# 07_-_GIGAVAC.net
KiCad netlist of a schematic drawn in Altium Designer
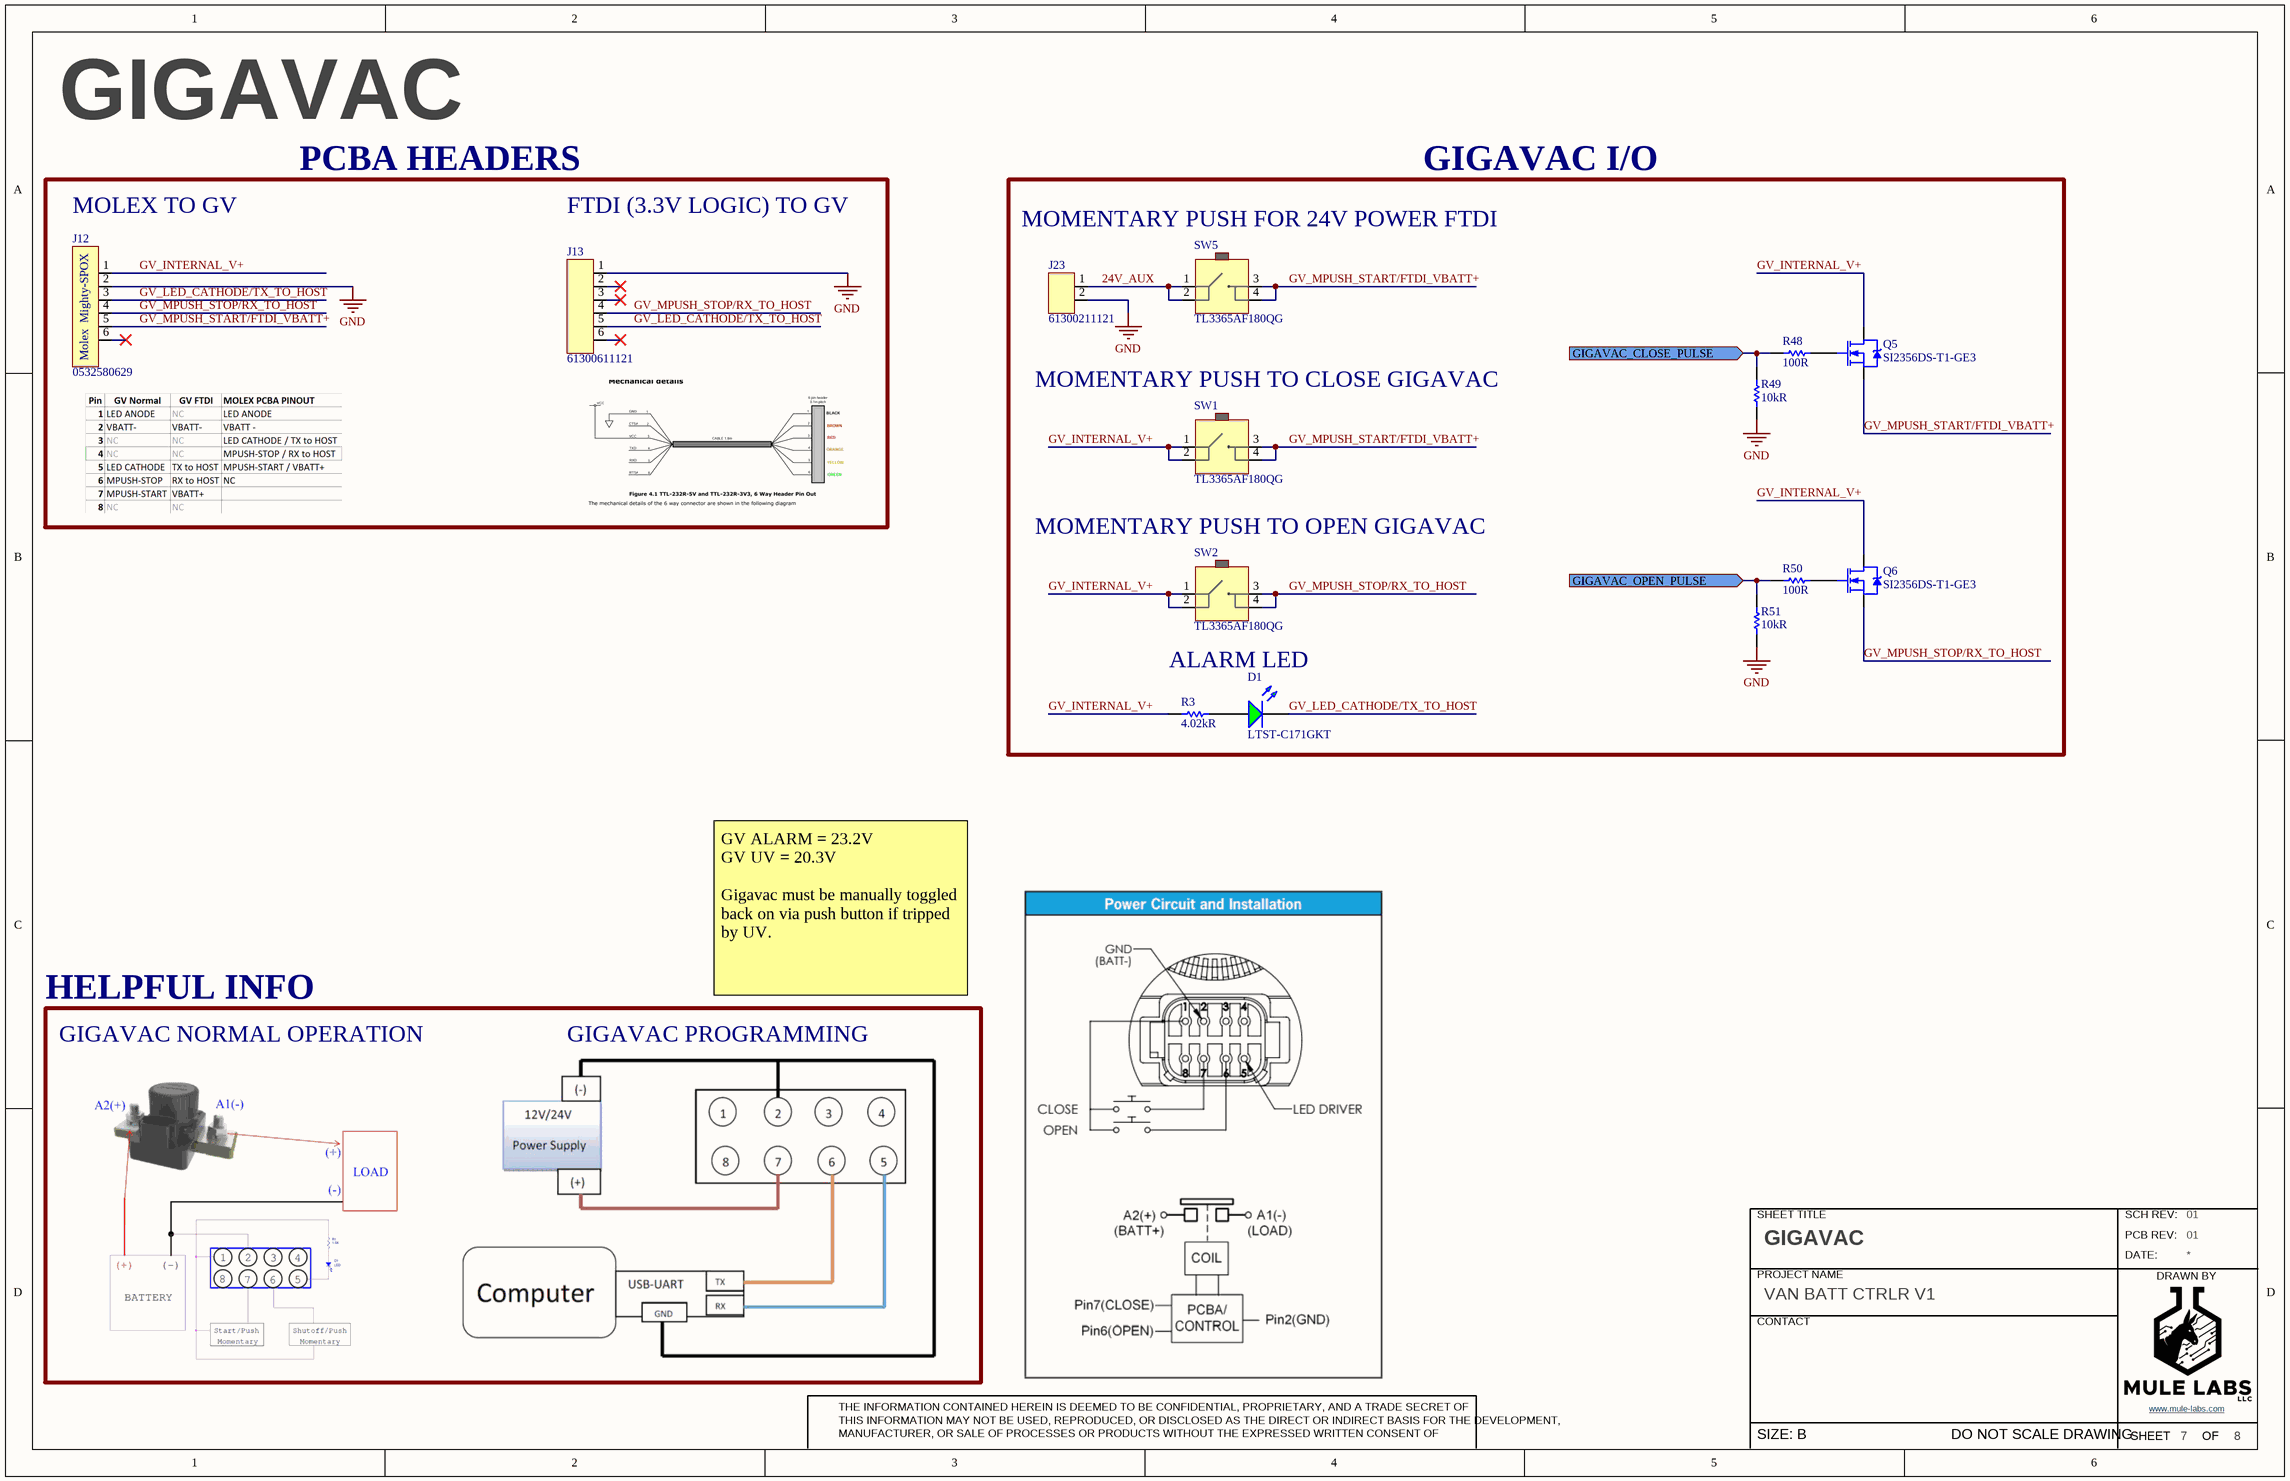
[diagram p0: [07] - GIGAVAC.SchDoc]

(export (version "E")
  (design (tool "Eeschema 10.0.6"))
  (components
    (comp (ref "D1")
      (value "LTST-C171GKT")
      (footprint "LED - 0805 - GREEN")
      (fields (field (name "MANUFACTURER") "Vishay Lite-On"))
      (libsource (lib "LEDs") (part "LTST-C171GKT"))
    )
    (comp (ref "J12")
      (value "0532580629")
      (footprint "MOLEX_532580629")
      (description "Mighty-SPOX Header, 3.50mm Pitch, Vertical, 6 Circuits, Brass (CuZn) Contact")
      (fields (field (name "MANUFACTURER") "Molex"))
      (libsource (lib "Connectors") (part "0532580629"))
    )
    (comp (ref "J13")
      (value "61300611121")
      (footprint "WURTH_61300611121")
      (description "CONN HEADER 6 POS 2.54")
      (fields (field (name "MANUFACTURER") "Wurth Electronics"))
      (libsource (lib "Connectors - Headers") (part "61300611121"))
    )
    (comp (ref "J23")
      (value "61300211121")
      (footprint "WURTH_61300211121")
      (description "CONN HEADER 2 POS 2.54")
      (fields (field (name "MANUFACTURER") "Wurth Electronics"))
      (libsource (lib "Connectors - Headers") (part "61300211121"))
    )
    (comp (ref "Q5")
      (value "SI2356DS-T1-GE3")
      (footprint "SOT23-3P95_237X112L50X42N")
      (description "Si2356DS Series 40 V 3.2 A 51 mOhm Surface Mount N-Channel Mosfet - SOT-23-3")
      (fields (field (name "MANUFACTURER") "Vishay Siliconix"))
      (libsource (lib "Transistors - FET") (part "SI2356DS-T1-GE3"))
    )
    (comp (ref "Q6")
      (value "SI2356DS-T1-GE3")
      (footprint "SOT23-3P95_237X112L50X42N")
      (description "Si2356DS Series 40 V 3.2 A 51 mOhm Surface Mount N-Channel Mosfet - SOT-23-3")
      (fields (field (name "MANUFACTURER") "Vishay Siliconix"))
      (libsource (lib "Transistors - FET") (part "SI2356DS-T1-GE3"))
    )
    (comp (ref "R3")
      (value "4.02kR")
      (footprint "INCH 0805 - METRIC 2012 - H065")
      (description "RES 4.02K OHM 1% 1/8W 0805")
      (fields
        (field (name "MANUFACTURER") "Stackpole Electronics")
        (field (name "MANUFACTURER PART NUMBER") "RMCF0805FT4K02")
      )
      (libsource (lib "Resistors") (part "RMCF0805FT4K02"))
    )
    (comp (ref "R48")
      (value "100R")
      (footprint "INCH 0603 - METRIC 1608 - H055")
      (description "RES SMD 100 OHM 0.1% 1/16W 0603")
      (fields
        (field (name "MANUFACTURER") "TE Connectivity Neohm")
        (field (name "MANUFACTURER PART NUMBER") "CPF0603B100RE1")
      )
      (libsource (lib "Resistors") (part "CPF0603B100RE1"))
    )
    (comp (ref "R49")
      (value "10kR")
      (footprint "INCH 0603 - METRIC 1508 - H050")
      (description "RES SMD 10K OHM 0.5% 1/16W 0603")
      (fields
        (field (name "MANUFACTURER") "Susumu")
        (field (name "MANUFACTURER PART NUMBER") "RR0816P-103-D")
      )
      (libsource (lib "Resistors") (part "RR0816P-103-D"))
    )
    (comp (ref "R50")
      (value "100R")
      (footprint "INCH 0603 - METRIC 1608 - H055")
      (description "RES SMD 100 OHM 0.1% 1/16W 0603")
      (fields
        (field (name "MANUFACTURER") "TE Connectivity Neohm")
        (field (name "MANUFACTURER PART NUMBER") "CPF0603B100RE1")
      )
      (libsource (lib "Resistors") (part "CPF0603B100RE1"))
    )
    (comp (ref "R51")
      (value "10kR")
      (footprint "INCH 0603 - METRIC 1508 - H050")
      (description "RES SMD 10K OHM 0.5% 1/16W 0603")
      (fields
        (field (name "MANUFACTURER") "Susumu")
        (field (name "MANUFACTURER PART NUMBER") "RR0816P-103-D")
      )
      (libsource (lib "Resistors") (part "RR0816P-103-D"))
    )
    (comp (ref "SW1")
      (value "TL3365AF180QG")
      (footprint "ESWITCH_TL3365AF180QG")
      (description "SWITCH TACTILE SPST-NO 0.05A 12V")
      (fields (field (name "MANUFACTURER") "E-Switch"))
      (libsource (lib "Switches") (part "TL3365AF180QG"))
    )
    (comp (ref "SW2")
      (value "TL3365AF180QG")
      (footprint "ESWITCH_TL3365AF180QG")
      (description "SWITCH TACTILE SPST-NO 0.05A 12V")
      (fields (field (name "MANUFACTURER") "E-Switch"))
      (libsource (lib "Switches") (part "TL3365AF180QG"))
    )
    (comp (ref "SW5")
      (value "TL3365AF180QG")
      (footprint "ESWITCH_TL3365AF180QG")
      (description "SWITCH TACTILE SPST-NO 0.05A 12V")
      (fields (field (name "MANUFACTURER") "E-Switch"))
      (libsource (lib "Switches") (part "TL3365AF180QG"))
    )
  )
  (nets
    (net (code "1") (name "/24V_AUX") (class "Default")
      (node (ref "J23") (pin "1") (pintype "passive"))
      (node (ref "SW5") (pin "1") (pinfunction "1_1") (pintype "passive"))
      (node (ref "SW5") (pin "2") (pinfunction "2_2") (pintype "passive"))
    )
    (net (code "2") (name "/GIGAVAC_CLOSE_PULSE") (class "Default")
      (node (ref "R48") (pin "1") (pintype "passive"))
      (node (ref "R49") (pin "2") (pintype "passive"))
    )
    (net (code "3") (name "/GIGAVAC_OPEN_PULSE") (class "Default")
      (node (ref "R50") (pin "1") (pintype "passive"))
      (node (ref "R51") (pin "2") (pintype "passive"))
    )
    (net (code "4") (name "/GV_INTERNAL_V+") (class "Default")
      (node (ref "J12") (pin "1") (pintype "passive"))
      (node (ref "Q5") (pin "3") (pinfunction "D_3") (pintype "passive"))
      (node (ref "Q6") (pin "3") (pinfunction "D_3") (pintype "passive"))
      (node (ref "R3") (pin "1") (pintype "passive"))
      (node (ref "SW1") (pin "1") (pinfunction "1_1") (pintype "passive"))
      (node (ref "SW1") (pin "2") (pinfunction "2_2") (pintype "passive"))
      (node (ref "SW2") (pin "1") (pinfunction "1_1") (pintype "passive"))
      (node (ref "SW2") (pin "2") (pinfunction "2_2") (pintype "passive"))
    )
    (net (code "5") (name "/GV_LED_CATHODE{slash}TX_TO_HOST") (class "Default")
      (node (ref "D1") (pin "C") (pintype "passive"))
      (node (ref "J12") (pin "3") (pintype "passive"))
      (node (ref "J13") (pin "5") (pintype "passive"))
    )
    (net (code "6") (name "/GV_MPUSH_START{slash}FTDI_VBATT+") (class "Default")
      (node (ref "J12") (pin "5") (pintype "passive"))
      (node (ref "Q5") (pin "2") (pinfunction "S_2") (pintype "passive"))
      (node (ref "SW1") (pin "3") (pinfunction "3_3") (pintype "passive"))
      (node (ref "SW1") (pin "4") (pinfunction "4_4") (pintype "passive"))
      (node (ref "SW5") (pin "3") (pinfunction "3_3") (pintype "passive"))
      (node (ref "SW5") (pin "4") (pinfunction "4_4") (pintype "passive"))
    )
    (net (code "7") (name "/GV_MPUSH_STOP{slash}RX_TO_HOST") (class "Default")
      (node (ref "J12") (pin "4") (pintype "passive"))
      (node (ref "J13") (pin "4") (pintype "passive"))
      (node (ref "Q6") (pin "2") (pinfunction "S_2") (pintype "passive"))
      (node (ref "SW2") (pin "3") (pinfunction "3_3") (pintype "passive"))
      (node (ref "SW2") (pin "4") (pinfunction "4_4") (pintype "passive"))
    )
    (net (code "8") (name "GND") (class "Default")
      (node (ref "J12") (pin "2") (pintype "passive"))
      (node (ref "J13") (pin "1") (pintype "passive"))
      (node (ref "J23") (pin "2") (pintype "passive"))
      (node (ref "R49") (pin "1") (pintype "passive"))
      (node (ref "R51") (pin "1") (pintype "passive"))
    )
    (net (code "9") (name "Net-(D1-PadA)") (class "Default")
      (node (ref "D1") (pin "A") (pintype "passive"))
      (node (ref "R3") (pin "2") (pintype "passive"))
    )
    (net (code "10") (name "Net-(Q5-G)") (class "Default")
      (node (ref "Q5") (pin "1") (pinfunction "G_1") (pintype "passive"))
      (node (ref "R48") (pin "2") (pintype "passive"))
    )
    (net (code "11") (name "Net-(Q6-G)") (class "Default")
      (node (ref "Q6") (pin "1") (pinfunction "G_1") (pintype "passive"))
      (node (ref "R50") (pin "2") (pintype "passive"))
    )
    (net (code "12") (name "unconnected-(J12-Pad6)") (class "Default")
      (node (ref "J12") (pin "6") (pintype "passive+no_connect"))
    )
    (net (code "13") (name "unconnected-(J13-Pad2)") (class "Default")
      (node (ref "J13") (pin "2") (pintype "passive+no_connect"))
    )
    (net (code "14") (name "unconnected-(J13-Pad3)") (class "Default")
      (node (ref "J13") (pin "3") (pintype "passive+no_connect"))
    )
    (net (code "15") (name "unconnected-(J13-Pad6)") (class "Default")
      (node (ref "J13") (pin "6") (pintype "passive+no_connect"))
    )
  )
)
